# ESP32.net
KiCad netlist of a schematic drawn in Altium Designer
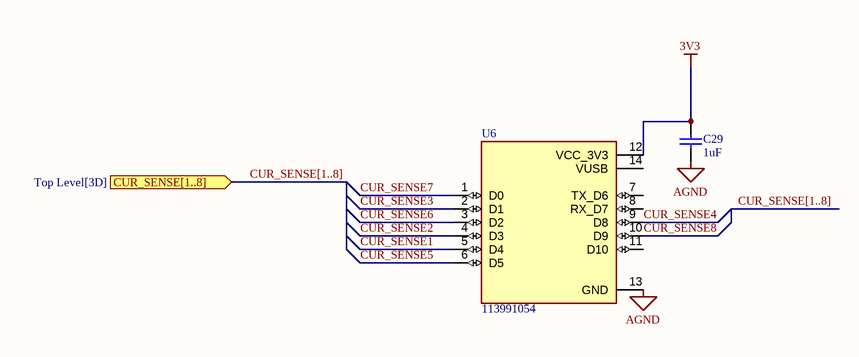
[diagram p0: ESP32.SchDoc]

(export (version "E")
  (design (tool "Eeschema 10.0.6"))
  (components
    (comp (ref "C29") (value "1uF") (footprint "0603") (libsource (lib "SamlibSCH") (part "C TBD 0603")))
    (comp (ref "U6")
      (value "113991054")
      (footprint "113991054")
      (fields (field (name "MF") "Seeed Technology Co., Ltd"))
      (libsource (lib "Schlib1") (part "113991054"))
    )
  )
  (nets
    (net (code "1") (name "/CUR_SENSE1") (class "Default")
      (node (ref "U6") (pin "5") (pinfunction "D4_5") (pintype "bidirectional"))
    )
    (net (code "2") (name "/CUR_SENSE2") (class "Default")
      (node (ref "U6") (pin "4") (pinfunction "D3_4") (pintype "bidirectional"))
    )
    (net (code "3") (name "/CUR_SENSE3") (class "Default")
      (node (ref "U6") (pin "2") (pinfunction "D1_2") (pintype "bidirectional"))
    )
    (net (code "4") (name "/CUR_SENSE4") (class "Default")
      (node (ref "U6") (pin "9") (pinfunction "D8_9") (pintype "bidirectional"))
    )
    (net (code "5") (name "/CUR_SENSE5") (class "Default")
      (node (ref "U6") (pin "6") (pinfunction "D5_6") (pintype "bidirectional"))
    )
    (net (code "6") (name "/CUR_SENSE6") (class "Default")
      (node (ref "U6") (pin "3") (pinfunction "D2_3") (pintype "bidirectional"))
    )
    (net (code "7") (name "/CUR_SENSE7") (class "Default")
      (node (ref "U6") (pin "1") (pinfunction "D0_1") (pintype "bidirectional"))
    )
    (net (code "8") (name "/CUR_SENSE8") (class "Default")
      (node (ref "U6") (pin "10") (pinfunction "D9_10") (pintype "bidirectional"))
    )
    (net (code "10") (name "3V3") (class "Default")
      (node (ref "C29") (pin "2") (pinfunction "2_2") (pintype "passive"))
      (node (ref "U6") (pin "12") (pinfunction "VCC_3V3_12") (pintype "power_in"))
    )
    (net (code "11") (name "AGND") (class "Default")
      (node (ref "C29") (pin "1") (pinfunction "1_1") (pintype "passive"))
      (node (ref "U6") (pin "13") (pinfunction "GND_13") (pintype "power_in"))
    )
    (net (code "12") (name "unconnected-(U6-D10-Pad11)") (class "Default")
      (node (ref "U6") (pin "11") (pinfunction "D10_11") (pintype "bidirectional"))
    )
    (net (code "13") (name "unconnected-(U6-RX_D7-Pad8)") (class "Default")
      (node (ref "U6") (pin "8") (pinfunction "RX_D7_8") (pintype "bidirectional"))
    )
    (net (code "14") (name "unconnected-(U6-TX_D6-Pad7)") (class "Default")
      (node (ref "U6") (pin "7") (pinfunction "TX_D6_7") (pintype "bidirectional"))
    )
    (net (code "15") (name "unconnected-(U6-VUSB-Pad14)") (class "Default")
      (node (ref "U6") (pin "14") (pinfunction "VUSB_14") (pintype "power_in"))
    )
  )
)
